# FRONT_PS.net
KiCad netlist of a schematic drawn in Altium Designer
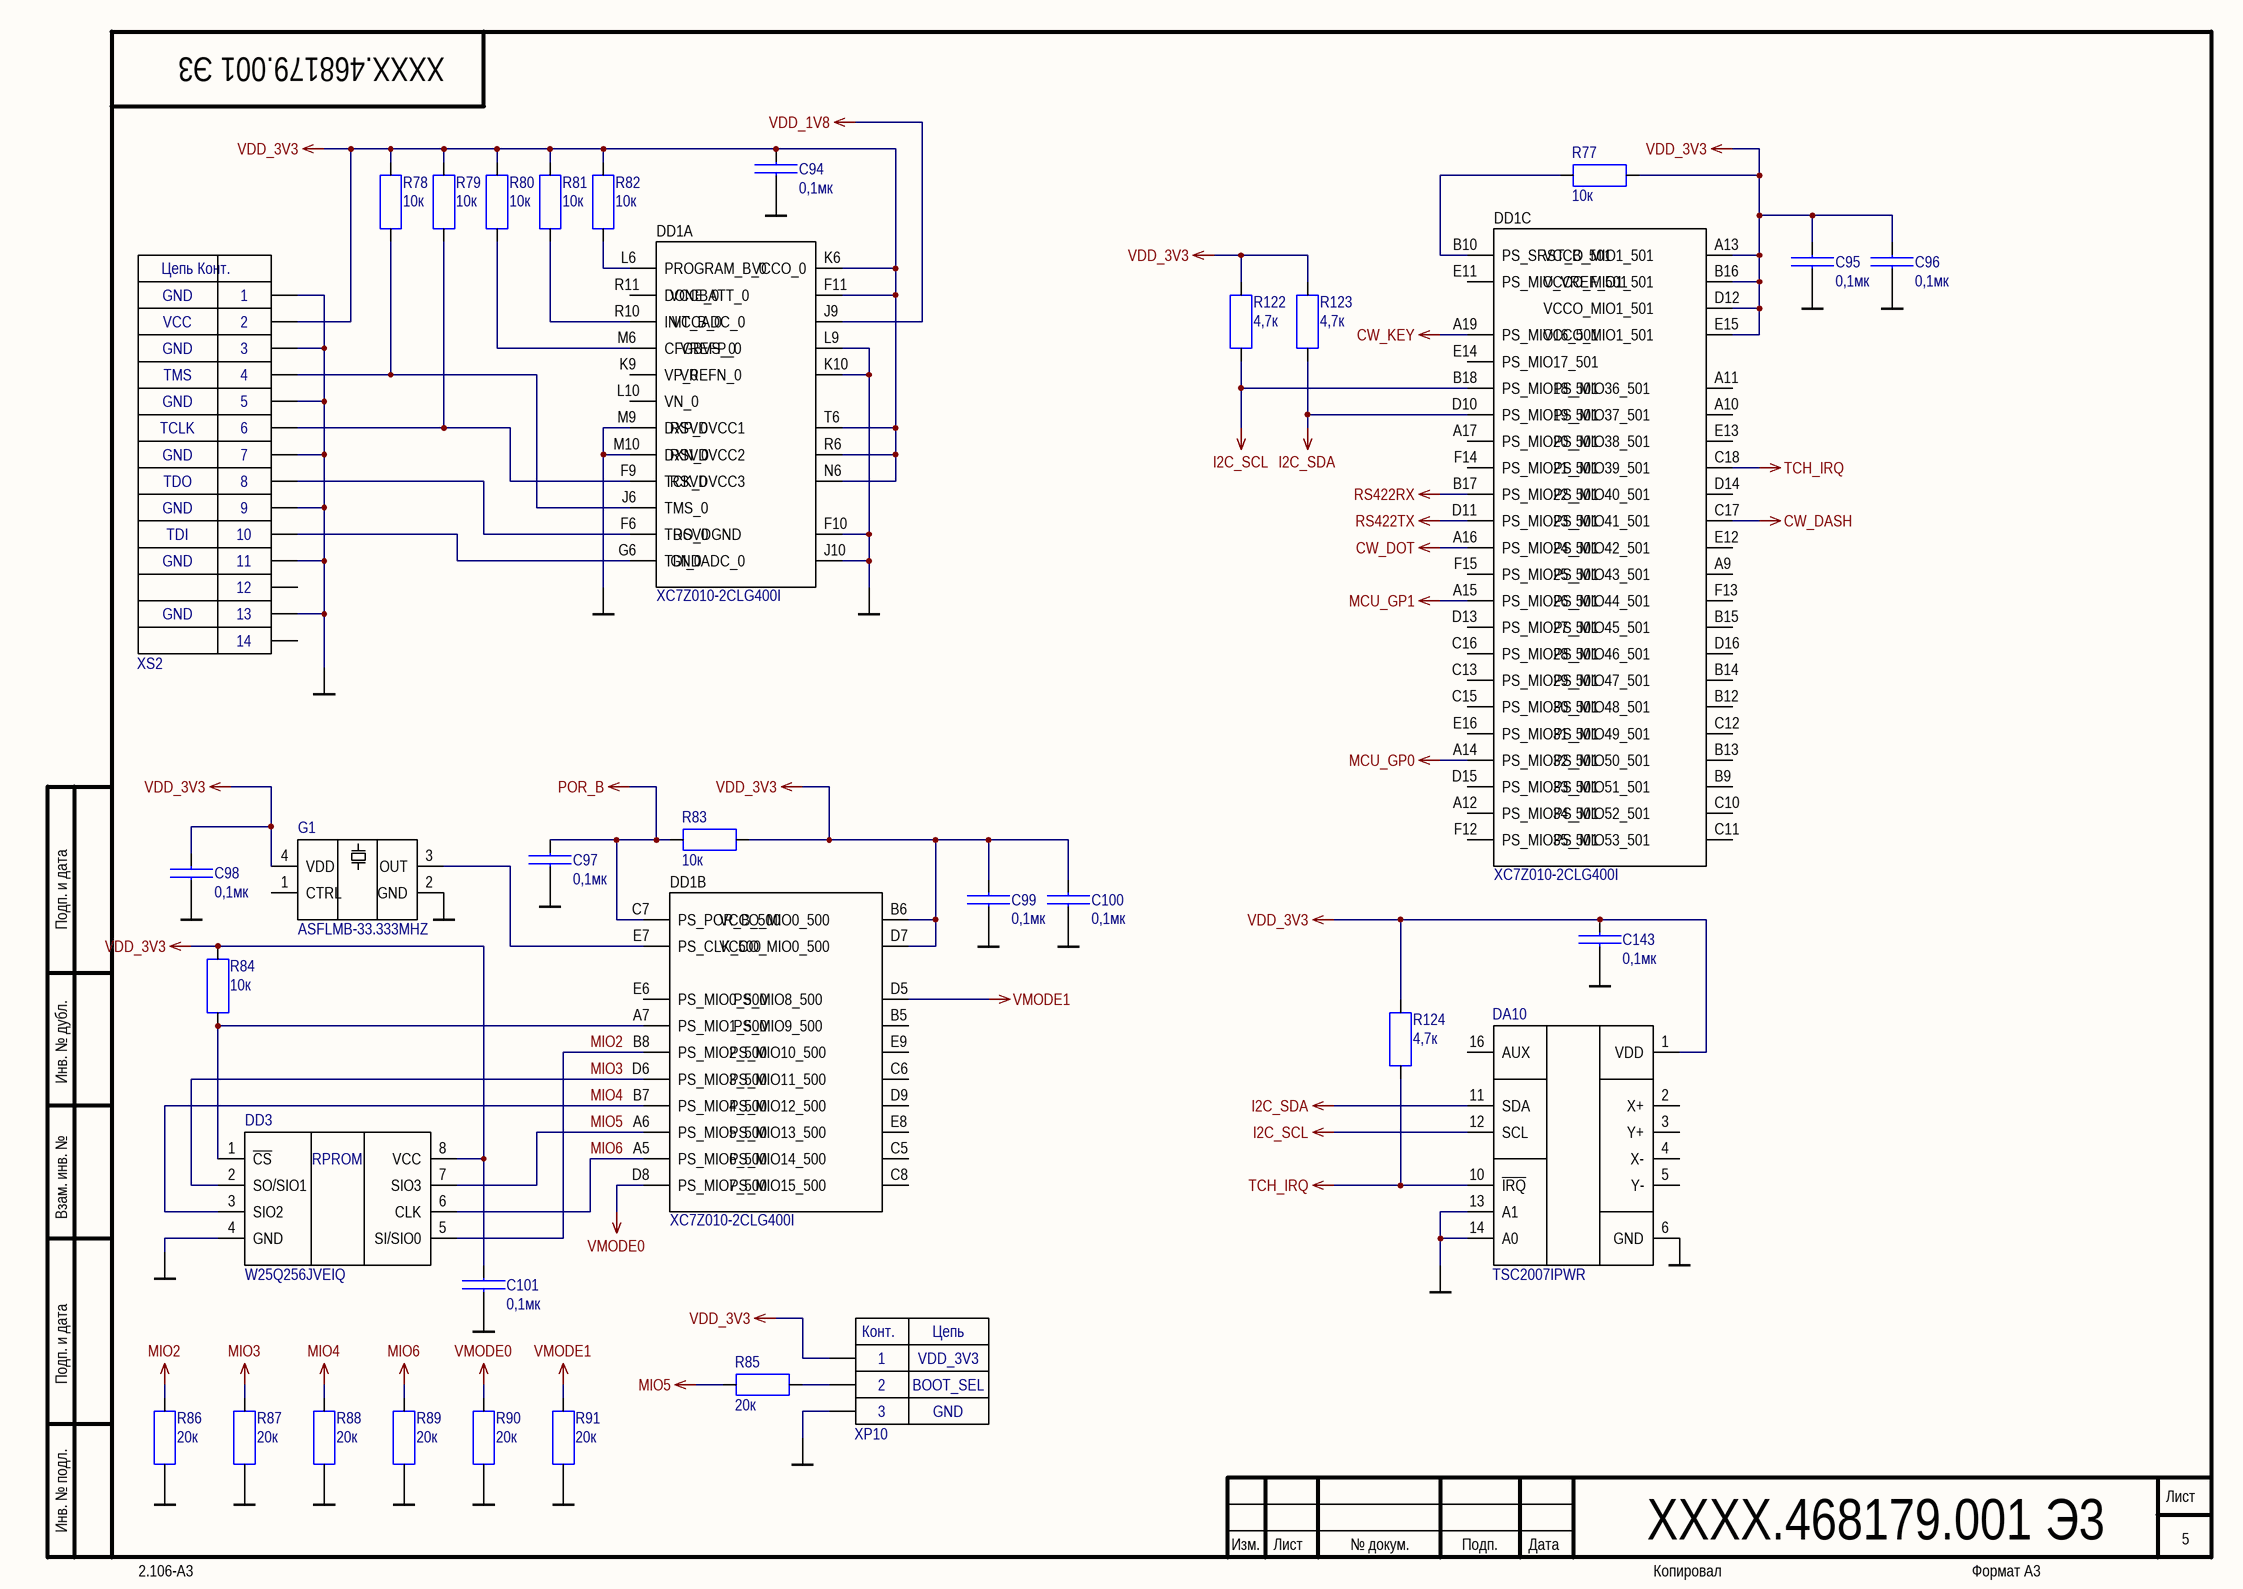
[diagram p0: FRONT_PS.SchDoc]

(export (version "E")
  (design (tool "Eeschema 10.0.6"))
  (components
    (comp (ref "C94")
      (value "CC0402KRX5R6BB104")
      (footprint "CAPC1005X05L")
      (description "ЧИП конденсатор")
      (fields
        (field (name "NOMINAL") "0,1мк")
        (field (name "MANUFACTURER") "Yageo")
        (field (name "TOLERANCE") "10%")
      )
      (libsource (lib "Database_Gost") (part "Capacitor const"))
    )
    (comp (ref "C95")
      (value "CC0402KRX5R6BB104")
      (footprint "CAPC1005X05L")
      (description "ЧИП конденсатор")
      (fields
        (field (name "NOMINAL") "0,1мк")
        (field (name "MANUFACTURER") "Yageo")
        (field (name "TOLERANCE") "10%")
      )
      (libsource (lib "Database_Gost") (part "Capacitor const"))
    )
    (comp (ref "C96")
      (value "CC0402KRX5R6BB104")
      (footprint "CAPC1005X05L")
      (description "ЧИП конденсатор")
      (fields
        (field (name "NOMINAL") "0,1мк")
        (field (name "MANUFACTURER") "Yageo")
        (field (name "TOLERANCE") "10%")
      )
      (libsource (lib "Database_Gost") (part "Capacitor const"))
    )
    (comp (ref "C97")
      (value "CC0402KRX5R6BB104")
      (footprint "CAPC1005X05L")
      (description "ЧИП конденсатор")
      (fields
        (field (name "NOMINAL") "0,1мк")
        (field (name "MANUFACTURER") "Yageo")
        (field (name "TOLERANCE") "10%")
      )
      (libsource (lib "Database_Gost") (part "Capacitor const"))
    )
    (comp (ref "C98")
      (value "CC0402KRX5R6BB104")
      (footprint "CAPC1005X05L")
      (description "ЧИП конденсатор")
      (fields
        (field (name "NOMINAL") "0,1мк")
        (field (name "MANUFACTURER") "Yageo")
        (field (name "TOLERANCE") "10%")
      )
      (libsource (lib "Database_Gost") (part "Capacitor const"))
    )
    (comp (ref "C99")
      (value "CC0402KRX5R6BB104")
      (footprint "CAPC1005X05L")
      (description "ЧИП конденсатор")
      (fields
        (field (name "NOMINAL") "0,1мк")
        (field (name "MANUFACTURER") "Yageo")
        (field (name "TOLERANCE") "10%")
      )
      (libsource (lib "Database_Gost") (part "Capacitor const"))
    )
    (comp (ref "C100")
      (value "CC0402KRX5R6BB104")
      (footprint "CAPC1005X05L")
      (description "ЧИП конденсатор")
      (fields
        (field (name "NOMINAL") "0,1мк")
        (field (name "MANUFACTURER") "Yageo")
        (field (name "TOLERANCE") "10%")
      )
      (libsource (lib "Database_Gost") (part "Capacitor const"))
    )
    (comp (ref "C101")
      (value "CC0402KRX5R6BB104")
      (footprint "CAPC1005X05L")
      (description "ЧИП конденсатор")
      (fields
        (field (name "NOMINAL") "0,1мк")
        (field (name "MANUFACTURER") "Yageo")
        (field (name "TOLERANCE") "10%")
      )
      (libsource (lib "Database_Gost") (part "Capacitor const"))
    )
    (comp (ref "C143")
      (value "CC0402KRX5R6BB104")
      (footprint "CAPC1005X05L")
      (description "ЧИП конденсатор")
      (fields
        (field (name "NOMINAL") "0,1мк")
        (field (name "MANUFACTURER") "Yageo")
        (field (name "TOLERANCE") "10%")
      )
      (libsource (lib "Database_Gost") (part "Capacitor const"))
    )
    (comp (ref "DA10")
      (value "TSC2007IPWR")
      (footprint "TSOP65P640X120-16N")
      (description "1.2V to 3.6V, 12-Bit, Nanopower, 4-Wire Micro TOUCH SCREEN CONTROLLER with I\r\n2C™ Interface")
      (fields (field (name "MANUFACTURER") "TI"))
      (libsource (lib "Chips_single") (part "TSC2007IPWR"))
    )
    (comp (ref "DD1")
      (value "XC7Z010-2CLG400I")
      (footprint "BGA400C80P20X20_1700X1700X147")
      (description "Zynq®-7000 SoC Family")
      (fields (field (name "MANUFACTURER") "Xilinx"))
      (libsource (lib "Chips_single") (part "XC7Z010-2CLG400I"))
    )
    (comp (ref "DD3")
      (value "W25Q256JVEIQ")
      (footprint "SON127P800X70_HS-9N")
      (description "3V 256M-BIT SERIAL FLASH MEMORY WITH DUAL/QUAD SPI")
      (fields (field (name "MANUFACTURER") "WINBOND"))
      (libsource (lib "Chips_single") (part "W25Q256JVEIQ"))
    )
    (comp (ref "G1")
      (value "ASFLMB-33.333MHZ")
      (footprint "XTAL_ASFLMB-33.333MHZ-LC-T")
      (description "33.333 MHz HCMOS/TTL Clock Oscillator")
      (fields
        (field (name "MANUFACTURER") "Abracom")
        (field (name "MANUFACTURERPARTNUMBER") "ASFLMB-33.333MHZ-LC")
      )
      (libsource (lib "Chips_single") (part "Генератор кварцевый ASFLMB-33.333MHZ"))
    )
    (comp (ref "R77")
      (value "RC0402JR-0710KL")
      (footprint "RESC1005X04L")
      (description "ЧИП резистор")
      (fields
        (field (name "NOMINAL") "10к")
        (field (name "MANUFACTURER") "Yageo")
        (field (name "TOLERANCE") "5%")
      )
      (libsource (lib "Database_Gost") (part "Resistor const"))
    )
    (comp (ref "R78")
      (value "RC0402JR-0710KL")
      (footprint "RESC1005X04L")
      (description "ЧИП резистор")
      (fields
        (field (name "NOMINAL") "10к")
        (field (name "MANUFACTURER") "Yageo")
        (field (name "TOLERANCE") "5%")
      )
      (libsource (lib "Database_Gost") (part "Resistor const"))
    )
    (comp (ref "R79")
      (value "RC0402JR-0710KL")
      (footprint "RESC1005X04L")
      (description "ЧИП резистор")
      (fields
        (field (name "NOMINAL") "10к")
        (field (name "MANUFACTURER") "Yageo")
        (field (name "TOLERANCE") "5%")
      )
      (libsource (lib "Database_Gost") (part "Resistor const"))
    )
    (comp (ref "R80")
      (value "RC0402JR-0710KL")
      (footprint "RESC1005X04L")
      (description "ЧИП резистор")
      (fields
        (field (name "NOMINAL") "10к")
        (field (name "MANUFACTURER") "Yageo")
        (field (name "TOLERANCE") "5%")
      )
      (libsource (lib "Database_Gost") (part "Resistor const"))
    )
    (comp (ref "R81")
      (value "RC0402JR-0710KL")
      (footprint "RESC1005X04L")
      (description "ЧИП резистор")
      (fields
        (field (name "NOMINAL") "10к")
        (field (name "MANUFACTURER") "Yageo")
        (field (name "TOLERANCE") "5%")
      )
      (libsource (lib "Database_Gost") (part "Resistor const"))
    )
    (comp (ref "R82")
      (value "RC0402JR-0710KL")
      (footprint "RESC1005X04L")
      (description "ЧИП резистор")
      (fields
        (field (name "NOMINAL") "10к")
        (field (name "MANUFACTURER") "Yageo")
        (field (name "TOLERANCE") "5%")
      )
      (libsource (lib "Database_Gost") (part "Resistor const"))
    )
    (comp (ref "R83")
      (value "RC0402JR-0710KL")
      (footprint "RESC1005X04L")
      (description "ЧИП резистор")
      (fields
        (field (name "NOMINAL") "10к")
        (field (name "MANUFACTURER") "Yageo")
        (field (name "TOLERANCE") "5%")
      )
      (libsource (lib "Database_Gost") (part "Resistor const"))
    )
    (comp (ref "R84")
      (value "RC0402JR-0710KL")
      (footprint "RESC1005X04L")
      (description "ЧИП резистор")
      (fields
        (field (name "NOMINAL") "10к")
        (field (name "MANUFACTURER") "Yageo")
        (field (name "TOLERANCE") "5%")
      )
      (libsource (lib "Database_Gost") (part "Resistor const"))
    )
    (comp (ref "R85")
      (value "RC0402JR-0720KL")
      (footprint "RESC1005X04L")
      (description "ЧИП резистор")
      (fields
        (field (name "NOMINAL") "20к")
        (field (name "MANUFACTURER") "Yageo")
        (field (name "TOLERANCE") "5%")
      )
      (libsource (lib "Database_Gost") (part "Resistor const"))
    )
    (comp (ref "R86")
      (value "RC0402JR-0720KL")
      (footprint "RESC1005X04L")
      (description "ЧИП резистор")
      (fields
        (field (name "NOMINAL") "20к")
        (field (name "MANUFACTURER") "Yageo")
        (field (name "TOLERANCE") "5%")
      )
      (libsource (lib "Database_Gost") (part "Resistor const"))
    )
    (comp (ref "R87")
      (value "RC0402JR-0720KL")
      (footprint "RESC1005X04L")
      (description "ЧИП резистор")
      (fields
        (field (name "NOMINAL") "20к")
        (field (name "MANUFACTURER") "Yageo")
        (field (name "TOLERANCE") "5%")
      )
      (libsource (lib "Database_Gost") (part "Resistor const"))
    )
    (comp (ref "R88")
      (value "RC0402JR-0720KL")
      (footprint "RESC1005X04L")
      (description "ЧИП резистор")
      (fields
        (field (name "NOMINAL") "20к")
        (field (name "MANUFACTURER") "Yageo")
        (field (name "TOLERANCE") "5%")
      )
      (libsource (lib "Database_Gost") (part "Resistor const"))
    )
    (comp (ref "R89")
      (value "RC0402JR-0720KL")
      (footprint "RESC1005X04L")
      (description "ЧИП резистор")
      (fields
        (field (name "NOMINAL") "20к")
        (field (name "MANUFACTURER") "Yageo")
        (field (name "TOLERANCE") "5%")
      )
      (libsource (lib "Database_Gost") (part "Resistor const"))
    )
    (comp (ref "R90")
      (value "RC0402JR-0720KL")
      (footprint "RESC1005X04L")
      (description "ЧИП резистор")
      (fields
        (field (name "NOMINAL") "20к")
        (field (name "MANUFACTURER") "Yageo")
        (field (name "TOLERANCE") "5%")
      )
      (libsource (lib "Database_Gost") (part "Resistor const"))
    )
    (comp (ref "R91")
      (value "RC0402JR-0720KL")
      (footprint "RESC1005X04L")
      (description "ЧИП резистор")
      (fields
        (field (name "NOMINAL") "20к")
        (field (name "MANUFACTURER") "Yageo")
        (field (name "TOLERANCE") "5%")
      )
      (libsource (lib "Database_Gost") (part "Resistor const"))
    )
    (comp (ref "R122")
      (value "RC0402JR-074K7L")
      (footprint "RESC1005X04L")
      (description "ЧИП резистор")
      (fields
        (field (name "NOMINAL") "4,7к")
        (field (name "MANUFACTURER") "Yageo")
        (field (name "TOLERANCE") "5%")
      )
      (libsource (lib "Database_Gost") (part "Resistor const"))
    )
    (comp (ref "R123")
      (value "RC0402JR-074K7L")
      (footprint "RESC1005X04L")
      (description "ЧИП резистор")
      (fields
        (field (name "NOMINAL") "4,7к")
        (field (name "MANUFACTURER") "Yageo")
        (field (name "TOLERANCE") "5%")
      )
      (libsource (lib "Database_Gost") (part "Resistor const"))
    )
    (comp (ref "R124")
      (value "RC0402JR-074K7L")
      (footprint "RESC1005X04L")
      (description "ЧИП резистор")
      (fields
        (field (name "NOMINAL") "4,7к")
        (field (name "MANUFACTURER") "Yageo")
        (field (name "TOLERANCE") "5%")
      )
      (libsource (lib "Database_Gost") (part "Resistor const"))
    )
    (comp (ref "XP10")
      (value "PLS-3")
      (footprint "PLS-3 (DS1021-1x3)")
      (libsource (lib "Connectors") (part "PLS-3"))
    )
    (comp (ref "XS2")
      (value "IDC2-14MS")
      (footprint "IDC2-14MS")
      (libsource (lib "Connectors") (part "JTAG Xilinx IDC2-14MS"))
    )
  )
  (nets
    (net (code "1") (name "CW_DASH") (class "Default")
      (node (ref "DD1") (pin "C17") (pinfunction "PS_MIO41_501_C17") (pintype "passive"))
    )
    (net (code "2") (name "CW_DOT") (class "Default")
      (node (ref "DD1") (pin "A16") (pinfunction "PS_MIO24_501_A16") (pintype "passive"))
    )
    (net (code "3") (name "CW_KEY") (class "Default")
      (node (ref "DD1") (pin "A19") (pinfunction "PS_MIO16_501_A19") (pintype "passive"))
    )
    (net (code "4") (name "GND") (class "Default")
      (node (ref "C100") (pin "1") (pinfunction "1_1") (pintype "passive"))
      (node (ref "C101") (pin "1") (pinfunction "1_1") (pintype "passive"))
      (node (ref "C143") (pin "1") (pinfunction "1_1") (pintype "passive"))
      (node (ref "C94") (pin "1") (pinfunction "1_1") (pintype "passive"))
      (node (ref "C95") (pin "1") (pinfunction "1_1") (pintype "passive"))
      (node (ref "C96") (pin "1") (pinfunction "1_1") (pintype "passive"))
      (node (ref "C97") (pin "1") (pinfunction "1_1") (pintype "passive"))
      (node (ref "C98") (pin "1") (pinfunction "1_1") (pintype "passive"))
      (node (ref "C99") (pin "1") (pinfunction "1_1") (pintype "passive"))
      (node (ref "DA10") (pin "13") (pinfunction "A1_13") (pintype "passive"))
      (node (ref "DA10") (pin "14") (pinfunction "A0_14") (pintype "passive"))
      (node (ref "DA10") (pin "6") (pinfunction "GND_6") (pintype "passive"))
      (node (ref "DD1") (pin "F10") (pinfunction "RSVDGND_F10") (pintype "passive"))
      (node (ref "DD1") (pin "J10") (pinfunction "GNDADC_0_J10") (pintype "passive"))
      (node (ref "DD1") (pin "K10") (pinfunction "VREFN_0_K10") (pintype "passive"))
      (node (ref "DD1") (pin "L9") (pinfunction "VREFP_0_L9") (pintype "passive"))
      (node (ref "DD1") (pin "M10") (pinfunction "DXN_0_M10") (pintype "passive"))
      (node (ref "DD1") (pin "M9") (pinfunction "DXP_0_M9") (pintype "passive"))
      (node (ref "DD3") (pin "4") (pinfunction "GND_4") (pintype "passive"))
      (node (ref "G1") (pin "2") (pinfunction "GND_2") (pintype "passive"))
      (node (ref "R86") (pin "2") (pinfunction "2_2") (pintype "passive"))
      (node (ref "R87") (pin "2") (pinfunction "2_2") (pintype "passive"))
      (node (ref "R88") (pin "2") (pinfunction "2_2") (pintype "passive"))
      (node (ref "R89") (pin "2") (pinfunction "2_2") (pintype "passive"))
      (node (ref "R90") (pin "2") (pinfunction "2_2") (pintype "passive"))
      (node (ref "R91") (pin "2") (pinfunction "2_2") (pintype "passive"))
      (node (ref "XP10") (pin "3") (pinfunction "3_3") (pintype "passive"))
      (node (ref "XS2") (pin "1") (pinfunction "1_1") (pintype "passive"))
      (node (ref "XS2") (pin "11") (pinfunction "11_11") (pintype "passive"))
      (node (ref "XS2") (pin "13") (pinfunction "13_13") (pintype "passive"))
      (node (ref "XS2") (pin "3") (pinfunction "3_3") (pintype "passive"))
      (node (ref "XS2") (pin "5") (pinfunction "5_5") (pintype "passive"))
      (node (ref "XS2") (pin "7") (pinfunction "7_7") (pintype "passive"))
      (node (ref "XS2") (pin "9") (pinfunction "9_9") (pintype "passive"))
    )
    (net (code "5") (name "I2C_SCL") (class "Default")
      (node (ref "DA10") (pin "12") (pinfunction "SCL_12") (pintype "passive"))
      (node (ref "DD1") (pin "B18") (pinfunction "PS_MIO18_501_B18") (pintype "passive"))
      (node (ref "R122") (pin "1") (pinfunction "1_1") (pintype "passive"))
    )
    (net (code "6") (name "I2C_SDA") (class "Default")
      (node (ref "DA10") (pin "11") (pinfunction "SDA_11") (pintype "passive"))
      (node (ref "DD1") (pin "D10") (pinfunction "PS_MIO19_501_D10") (pintype "passive"))
      (node (ref "R123") (pin "1") (pinfunction "1_1") (pintype "passive"))
    )
    (net (code "7") (name "MCU_GP0") (class "Default")
      (node (ref "DD1") (pin "A14") (pinfunction "PS_MIO32_501_A14") (pintype "passive"))
    )
    (net (code "8") (name "MCU_GP1") (class "Default")
      (node (ref "DD1") (pin "A15") (pinfunction "PS_MIO26_501_A15") (pintype "passive"))
    )
    (net (code "9") (name "MIO2") (class "Default")
      (node (ref "DD1") (pin "B8") (pinfunction "PS_MIO2_500_B8") (pintype "passive"))
      (node (ref "DD3") (pin "5") (pinfunction "SI/SIO0_5") (pintype "passive"))
      (node (ref "R86") (pin "1") (pinfunction "1_1") (pintype "passive"))
    )
    (net (code "10") (name "MIO3") (class "Default")
      (node (ref "DD1") (pin "D6") (pinfunction "PS_MIO3_500_D6") (pintype "passive"))
      (node (ref "DD3") (pin "2") (pinfunction "SO/SIO1_2") (pintype "passive"))
      (node (ref "R87") (pin "1") (pinfunction "1_1") (pintype "passive"))
    )
    (net (code "11") (name "MIO4") (class "Default")
      (node (ref "DD1") (pin "B7") (pinfunction "PS_MIO4_500_B7") (pintype "passive"))
      (node (ref "DD3") (pin "3") (pinfunction "SIO2_3") (pintype "passive"))
      (node (ref "R88") (pin "1") (pinfunction "1_1") (pintype "passive"))
    )
    (net (code "12") (name "MIO5") (class "Default")
      (node (ref "DD1") (pin "A6") (pinfunction "PS_MIO5_500_A6") (pintype "passive"))
      (node (ref "DD3") (pin "7") (pinfunction "SIO3_7") (pintype "passive"))
      (node (ref "R85") (pin "1") (pinfunction "1_1") (pintype "passive"))
    )
    (net (code "13") (name "MIO6") (class "Default")
      (node (ref "DD1") (pin "A5") (pinfunction "PS_MIO6_500_A5") (pintype "passive"))
      (node (ref "DD3") (pin "6") (pinfunction "CLK_6") (pintype "passive"))
      (node (ref "R89") (pin "1") (pinfunction "1_1") (pintype "passive"))
    )
    (net (code "14") (name "Net-(DD1A-CFGBVS_0)") (class "Default")
      (node (ref "DD1") (pin "M6") (pinfunction "CFGBVS_0_M6") (pintype "passive"))
      (node (ref "R80") (pin "1") (pinfunction "1_1") (pintype "passive"))
    )
    (net (code "15") (name "Net-(DD1A-INIT_B_0)") (class "Default")
      (node (ref "DD1") (pin "R10") (pinfunction "INIT_B_0_R10") (pintype "passive"))
      (node (ref "R81") (pin "1") (pinfunction "1_1") (pintype "passive"))
    )
    (net (code "16") (name "Net-(DD1A-PROGRAM_B_0)") (class "Default")
      (node (ref "DD1") (pin "L6") (pinfunction "PROGRAM_B_0_L6") (pintype "passive"))
      (node (ref "R82") (pin "1") (pinfunction "1_1") (pintype "passive"))
    )
    (net (code "17") (name "Net-(DD1A-TCK_0)") (class "Default")
      (node (ref "DD1") (pin "F9") (pinfunction "TCK_0_F9") (pintype "passive"))
      (node (ref "R79") (pin "1") (pinfunction "1_1") (pintype "passive"))
      (node (ref "XS2") (pin "6") (pinfunction "6_6") (pintype "passive"))
    )
    (net (code "18") (name "Net-(DD1A-TDI_0)") (class "Default")
      (node (ref "DD1") (pin "G6") (pinfunction "TDI_0_G6") (pintype "passive"))
      (node (ref "XS2") (pin "10") (pinfunction "10_10") (pintype "passive"))
    )
    (net (code "19") (name "Net-(DD1A-TDO_0)") (class "Default")
      (node (ref "DD1") (pin "F6") (pinfunction "TDO_0_F6") (pintype "passive"))
      (node (ref "XS2") (pin "8") (pinfunction "8_8") (pintype "passive"))
    )
    (net (code "20") (name "Net-(DD1A-TMS_0)") (class "Default")
      (node (ref "DD1") (pin "J6") (pinfunction "TMS_0_J6") (pintype "passive"))
      (node (ref "R78") (pin "1") (pinfunction "1_1") (pintype "passive"))
      (node (ref "XS2") (pin "4") (pinfunction "4_4") (pintype "passive"))
    )
    (net (code "21") (name "Net-(DD1B-PS_CLK_500)") (class "Default")
      (node (ref "DD1") (pin "E7") (pinfunction "PS_CLK_500_E7") (pintype "passive"))
      (node (ref "G1") (pin "3") (pinfunction "OUT_3") (pintype "passive"))
    )
    (net (code "22") (name "Net-(DD1B-PS_MIO1_500)") (class "Default")
      (node (ref "DD1") (pin "A7") (pinfunction "PS_MIO1_500_A7") (pintype "passive"))
      (node (ref "DD3") (pin "1") (pinfunction "~{CS}_1") (pintype "passive"))
      (node (ref "R84") (pin "1") (pinfunction "1_1") (pintype "passive"))
    )
    (net (code "23") (name "Net-(DD1C-PS_SRST_B_501)") (class "Default")
      (node (ref "DD1") (pin "B10") (pinfunction "PS_SRST_B_501_B10") (pintype "passive"))
      (node (ref "R77") (pin "1") (pinfunction "1_1") (pintype "passive"))
    )
    (net (code "24") (name "Net-(R85-Pad2)") (class "Default")
      (node (ref "R85") (pin "2") (pinfunction "2_2") (pintype "passive"))
      (node (ref "XP10") (pin "2") (pinfunction "2_2") (pintype "passive"))
    )
    (net (code "25") (name "POR_B") (class "Default")
      (node (ref "C97") (pin "2") (pinfunction "2_2") (pintype "passive"))
      (node (ref "DD1") (pin "C7") (pinfunction "PS_POR_B_500_C7") (pintype "passive"))
      (node (ref "R83") (pin "1") (pinfunction "1_1") (pintype "passive"))
    )
    (net (code "26") (name "RS422RX") (class "Default")
      (node (ref "DD1") (pin "B17") (pinfunction "PS_MIO22_501_B17") (pintype "passive"))
    )
    (net (code "27") (name "RS422TX") (class "Default")
      (node (ref "DD1") (pin "D11") (pinfunction "PS_MIO23_501_D11") (pintype "passive"))
    )
    (net (code "28") (name "TCH_IRQ") (class "Default")
      (node (ref "DA10") (pin "10") (pinfunction "~{IRQ}_10") (pintype "passive"))
      (node (ref "DD1") (pin "C18") (pinfunction "PS_MIO39_501_C18") (pintype "passive"))
      (node (ref "R124") (pin "1") (pinfunction "1_1") (pintype "passive"))
    )
    (net (code "29") (name "VDD_1V8") (class "Default")
      (node (ref "DD1") (pin "J9") (pinfunction "VCCADC_0_J9") (pintype "passive"))
    )
    (net (code "30") (name "VDD_3V3") (class "Default")
      (node (ref "C100") (pin "2") (pinfunction "2_2") (pintype "passive"))
      (node (ref "C101") (pin "2") (pinfunction "2_2") (pintype "passive"))
      (node (ref "C143") (pin "2") (pinfunction "2_2") (pintype "passive"))
      (node (ref "C94") (pin "2") (pinfunction "2_2") (pintype "passive"))
      (node (ref "C95") (pin "2") (pinfunction "2_2") (pintype "passive"))
      (node (ref "C96") (pin "2") (pinfunction "2_2") (pintype "passive"))
      (node (ref "C98") (pin "2") (pinfunction "2_2") (pintype "passive"))
      (node (ref "C99") (pin "2") (pinfunction "2_2") (pintype "passive"))
      (node (ref "DA10") (pin "1") (pinfunction "VDD_1") (pintype "passive"))
      (node (ref "DD1") (pin "A13") (pinfunction "VCCO_MIO1_501_A13") (pintype "passive"))
      (node (ref "DD1") (pin "B16") (pinfunction "VCCO_MIO1_501_B16") (pintype "passive"))
      (node (ref "DD1") (pin "B6") (pinfunction "VCCO_MIO0_500_B6") (pintype "passive"))
      (node (ref "DD1") (pin "D12") (pinfunction "VCCO_MIO1_501_D12") (pintype "passive"))
      (node (ref "DD1") (pin "D7") (pinfunction "VCCO_MIO0_500_D7") (pintype "passive"))
      (node (ref "DD1") (pin "E15") (pinfunction "VCCO_MIO1_501_E15") (pintype "passive"))
      (node (ref "DD1") (pin "F11") (pinfunction "VCCBATT_0_F11") (pintype "passive"))
      (node (ref "DD1") (pin "K6") (pinfunction "VCCO_0_K6") (pintype "passive"))
      (node (ref "DD1") (pin "N6") (pinfunction "RSVDVCC3_N6") (pintype "passive"))
      (node (ref "DD1") (pin "R6") (pinfunction "RSVDVCC2_R6") (pintype "passive"))
      (node (ref "DD1") (pin "T6") (pinfunction "RSVDVCC1_T6") (pintype "passive"))
      (node (ref "DD3") (pin "8") (pinfunction "VCC_8") (pintype "passive"))
      (node (ref "G1") (pin "4") (pinfunction "VDD_4") (pintype "passive"))
      (node (ref "R122") (pin "2") (pinfunction "2_2") (pintype "passive"))
      (node (ref "R123") (pin "2") (pinfunction "2_2") (pintype "passive"))
      (node (ref "R124") (pin "2") (pinfunction "2_2") (pintype "passive"))
      (node (ref "R77") (pin "2") (pinfunction "2_2") (pintype "passive"))
      (node (ref "R78") (pin "2") (pinfunction "2_2") (pintype "passive"))
      (node (ref "R79") (pin "2") (pinfunction "2_2") (pintype "passive"))
      (node (ref "R80") (pin "2") (pinfunction "2_2") (pintype "passive"))
      (node (ref "R81") (pin "2") (pinfunction "2_2") (pintype "passive"))
      (node (ref "R82") (pin "2") (pinfunction "2_2") (pintype "passive"))
      (node (ref "R83") (pin "2") (pinfunction "2_2") (pintype "passive"))
      (node (ref "R84") (pin "2") (pinfunction "2_2") (pintype "passive"))
      (node (ref "XP10") (pin "1") (pinfunction "1_1") (pintype "passive"))
      (node (ref "XS2") (pin "2") (pinfunction "2_2") (pintype "passive"))
    )
    (net (code "31") (name "VMODE0") (class "Default")
      (node (ref "DD1") (pin "D8") (pinfunction "PS_MIO7_500_D8") (pintype "passive"))
      (node (ref "R90") (pin "1") (pinfunction "1_1") (pintype "passive"))
    )
    (net (code "32") (name "VMODE1") (class "Default")
      (node (ref "DD1") (pin "D5") (pinfunction "PS_MIO8_500_D5") (pintype "passive"))
      (node (ref "R91") (pin "1") (pinfunction "1_1") (pintype "passive"))
    )
    (net (code "33") (name "unconnected-(DA10-AUX-Pad16)") (class "Default")
      (node (ref "DA10") (pin "16") (pinfunction "AUX_16") (pintype "passive"))
    )
    (net (code "34") (name "unconnected-(DA10-X+-Pad2)") (class "Default")
      (node (ref "DA10") (pin "2") (pinfunction "X+_2") (pintype "passive"))
    )
    (net (code "35") (name "unconnected-(DA10-X--Pad4)") (class "Default")
      (node (ref "DA10") (pin "4") (pinfunction "X-_4") (pintype "passive"))
    )
    (net (code "36") (name "unconnected-(DA10-Y+-Pad3)") (class "Default")
      (node (ref "DA10") (pin "3") (pinfunction "Y+_3") (pintype "passive"))
    )
    (net (code "37") (name "unconnected-(DA10-Y--Pad5)") (class "Default")
      (node (ref "DA10") (pin "5") (pinfunction "Y-_5") (pintype "passive"))
    )
    (net (code "38") (name "unconnected-(DD1A-DONE_0-PadR11)") (class "Default")
      (node (ref "DD1") (pin "R11") (pinfunction "DONE_0_R11") (pintype "passive"))
    )
    (net (code "39") (name "unconnected-(DD1A-VN_0-PadL10)") (class "Default")
      (node (ref "DD1") (pin "L10") (pinfunction "VN_0_L10") (pintype "passive"))
    )
    (net (code "40") (name "unconnected-(DD1A-VP_0-PadK9)") (class "Default")
      (node (ref "DD1") (pin "K9") (pinfunction "VP_0_K9") (pintype "passive"))
    )
    (net (code "41") (name "unconnected-(DD1B-PS_MIO0_500-PadE6)") (class "Default")
      (node (ref "DD1") (pin "E6") (pinfunction "PS_MIO0_500_E6") (pintype "passive"))
    )
    (net (code "42") (name "unconnected-(DD1B-PS_MIO9_500-PadB5)") (class "Default")
      (node (ref "DD1") (pin "B5") (pinfunction "PS_MIO9_500_B5") (pintype "passive"))
    )
    (net (code "43") (name "unconnected-(DD1B-PS_MIO10_500-PadE9)") (class "Default")
      (node (ref "DD1") (pin "E9") (pinfunction "PS_MIO10_500_E9") (pintype "passive"))
    )
    (net (code "44") (name "unconnected-(DD1B-PS_MIO11_500-PadC6)") (class "Default")
      (node (ref "DD1") (pin "C6") (pinfunction "PS_MIO11_500_C6") (pintype "passive"))
    )
    (net (code "45") (name "unconnected-(DD1B-PS_MIO12_500-PadD9)") (class "Default")
      (node (ref "DD1") (pin "D9") (pinfunction "PS_MIO12_500_D9") (pintype "passive"))
    )
    (net (code "46") (name "unconnected-(DD1B-PS_MIO13_500-PadE8)") (class "Default")
      (node (ref "DD1") (pin "E8") (pinfunction "PS_MIO13_500_E8") (pintype "passive"))
    )
    (net (code "47") (name "unconnected-(DD1B-PS_MIO14_500-PadC5)") (class "Default")
      (node (ref "DD1") (pin "C5") (pinfunction "PS_MIO14_500_C5") (pintype "passive"))
    )
    (net (code "48") (name "unconnected-(DD1B-PS_MIO15_500-PadC8)") (class "Default")
      (node (ref "DD1") (pin "C8") (pinfunction "PS_MIO15_500_C8") (pintype "passive"))
    )
    (net (code "49") (name "unconnected-(DD1C-PS_MIO17_501-PadE14)") (class "Default")
      (node (ref "DD1") (pin "E14") (pinfunction "PS_MIO17_501_E14") (pintype "passive"))
    )
    (net (code "50") (name "unconnected-(DD1C-PS_MIO20_501-PadA17)") (class "Default")
      (node (ref "DD1") (pin "A17") (pinfunction "PS_MIO20_501_A17") (pintype "passive"))
    )
    (net (code "51") (name "unconnected-(DD1C-PS_MIO21_501-PadF14)") (class "Default")
      (node (ref "DD1") (pin "F14") (pinfunction "PS_MIO21_501_F14") (pintype "passive"))
    )
    (net (code "52") (name "unconnected-(DD1C-PS_MIO25_501-PadF15)") (class "Default")
      (node (ref "DD1") (pin "F15") (pinfunction "PS_MIO25_501_F15") (pintype "passive"))
    )
    (net (code "53") (name "unconnected-(DD1C-PS_MIO27_501-PadD13)") (class "Default")
      (node (ref "DD1") (pin "D13") (pinfunction "PS_MIO27_501_D13") (pintype "passive"))
    )
    (net (code "54") (name "unconnected-(DD1C-PS_MIO28_501-PadC16)") (class "Default")
      (node (ref "DD1") (pin "C16") (pinfunction "PS_MIO28_501_C16") (pintype "passive"))
    )
    (net (code "55") (name "unconnected-(DD1C-PS_MIO29_501-PadC13)") (class "Default")
      (node (ref "DD1") (pin "C13") (pinfunction "PS_MIO29_501_C13") (pintype "passive"))
    )
    (net (code "56") (name "unconnected-(DD1C-PS_MIO30_501-PadC15)") (class "Default")
      (node (ref "DD1") (pin "C15") (pinfunction "PS_MIO30_501_C15") (pintype "passive"))
    )
    (net (code "57") (name "unconnected-(DD1C-PS_MIO31_501-PadE16)") (class "Default")
      (node (ref "DD1") (pin "E16") (pinfunction "PS_MIO31_501_E16") (pintype "passive"))
    )
    (net (code "58") (name "unconnected-(DD1C-PS_MIO33_501-PadD15)") (class "Default")
      (node (ref "DD1") (pin "D15") (pinfunction "PS_MIO33_501_D15") (pintype "passive"))
    )
    (net (code "59") (name "unconnected-(DD1C-PS_MIO34_501-PadA12)") (class "Default")
      (node (ref "DD1") (pin "A12") (pinfunction "PS_MIO34_501_A12") (pintype "passive"))
    )
    (net (code "60") (name "unconnected-(DD1C-PS_MIO35_501-PadF12)") (class "Default")
      (node (ref "DD1") (pin "F12") (pinfunction "PS_MIO35_501_F12") (pintype "passive"))
    )
    (net (code "61") (name "unconnected-(DD1C-PS_MIO36_501-PadA11)") (class "Default")
      (node (ref "DD1") (pin "A11") (pinfunction "PS_MIO36_501_A11") (pintype "passive"))
    )
    (net (code "62") (name "unconnected-(DD1C-PS_MIO37_501-PadA10)") (class "Default")
      (node (ref "DD1") (pin "A10") (pinfunction "PS_MIO37_501_A10") (pintype "passive"))
    )
    (net (code "63") (name "unconnected-(DD1C-PS_MIO38_501-PadE13)") (class "Default")
      (node (ref "DD1") (pin "E13") (pinfunction "PS_MIO38_501_E13") (pintype "passive"))
    )
    (net (code "64") (name "unconnected-(DD1C-PS_MIO40_501-PadD14)") (class "Default")
      (node (ref "DD1") (pin "D14") (pinfunction "PS_MIO40_501_D14") (pintype "passive"))
    )
    (net (code "65") (name "unconnected-(DD1C-PS_MIO42_501-PadE12)") (class "Default")
      (node (ref "DD1") (pin "E12") (pinfunction "PS_MIO42_501_E12") (pintype "passive"))
    )
    (net (code "66") (name "unconnected-(DD1C-PS_MIO43_501-PadA9)") (class "Default")
      (node (ref "DD1") (pin "A9") (pinfunction "PS_MIO43_501_A9") (pintype "passive"))
    )
    (net (code "67") (name "unconnected-(DD1C-PS_MIO44_501-PadF13)") (class "Default")
      (node (ref "DD1") (pin "F13") (pinfunction "PS_MIO44_501_F13") (pintype "passive"))
    )
    (net (code "68") (name "unconnected-(DD1C-PS_MIO45_501-PadB15)") (class "Default")
      (node (ref "DD1") (pin "B15") (pinfunction "PS_MIO45_501_B15") (pintype "passive"))
    )
    (net (code "69") (name "unconnected-(DD1C-PS_MIO46_501-PadD16)") (class "Default")
      (node (ref "DD1") (pin "D16") (pinfunction "PS_MIO46_501_D16") (pintype "passive"))
    )
    (net (code "70") (name "unconnected-(DD1C-PS_MIO47_501-PadB14)") (class "Default")
      (node (ref "DD1") (pin "B14") (pinfunction "PS_MIO47_501_B14") (pintype "passive"))
    )
    (net (code "71") (name "unconnected-(DD1C-PS_MIO48_501-PadB12)") (class "Default")
      (node (ref "DD1") (pin "B12") (pinfunction "PS_MIO48_501_B12") (pintype "passive"))
    )
    (net (code "72") (name "unconnected-(DD1C-PS_MIO49_501-PadC12)") (class "Default")
      (node (ref "DD1") (pin "C12") (pinfunction "PS_MIO49_501_C12") (pintype "passive"))
    )
    (net (code "73") (name "unconnected-(DD1C-PS_MIO50_501-PadB13)") (class "Default")
      (node (ref "DD1") (pin "B13") (pinfunction "PS_MIO50_501_B13") (pintype "passive"))
    )
    (net (code "74") (name "unconnected-(DD1C-PS_MIO51_501-PadB9)") (class "Default")
      (node (ref "DD1") (pin "B9") (pinfunction "PS_MIO51_501_B9") (pintype "passive"))
    )
    (net (code "75") (name "unconnected-(DD1C-PS_MIO52_501-PadC10)") (class "Default")
      (node (ref "DD1") (pin "C10") (pinfunction "PS_MIO52_501_C10") (pintype "passive"))
    )
    (net (code "76") (name "unconnected-(DD1C-PS_MIO53_501-PadC11)") (class "Default")
      (node (ref "DD1") (pin "C11") (pinfunction "PS_MIO53_501_C11") (pintype "passive"))
    )
    (net (code "77") (name "unconnected-(DD1C-PS_MIO_VREF_501-PadE11)") (class "Default")
      (node (ref "DD1") (pin "E11") (pinfunction "PS_MIO_VREF_501_E11") (pintype "passive"))
    )
    (net (code "78") (name "unconnected-(G1-CTRL-Pad1)") (class "Default")
      (node (ref "G1") (pin "1") (pinfunction "CTRL_1") (pintype "passive"))
    )
    (net (code "79") (name "unconnected-(XS2-Pad12)") (class "Default")
      (node (ref "XS2") (pin "12") (pinfunction "12_12") (pintype "passive"))
    )
    (net (code "80") (name "unconnected-(XS2-Pad14)") (class "Default")
      (node (ref "XS2") (pin "14") (pinfunction "14_14") (pintype "passive"))
    )
  )
)
